# schematic.net
KiCad netlist of a schematic drawn in EAGLE
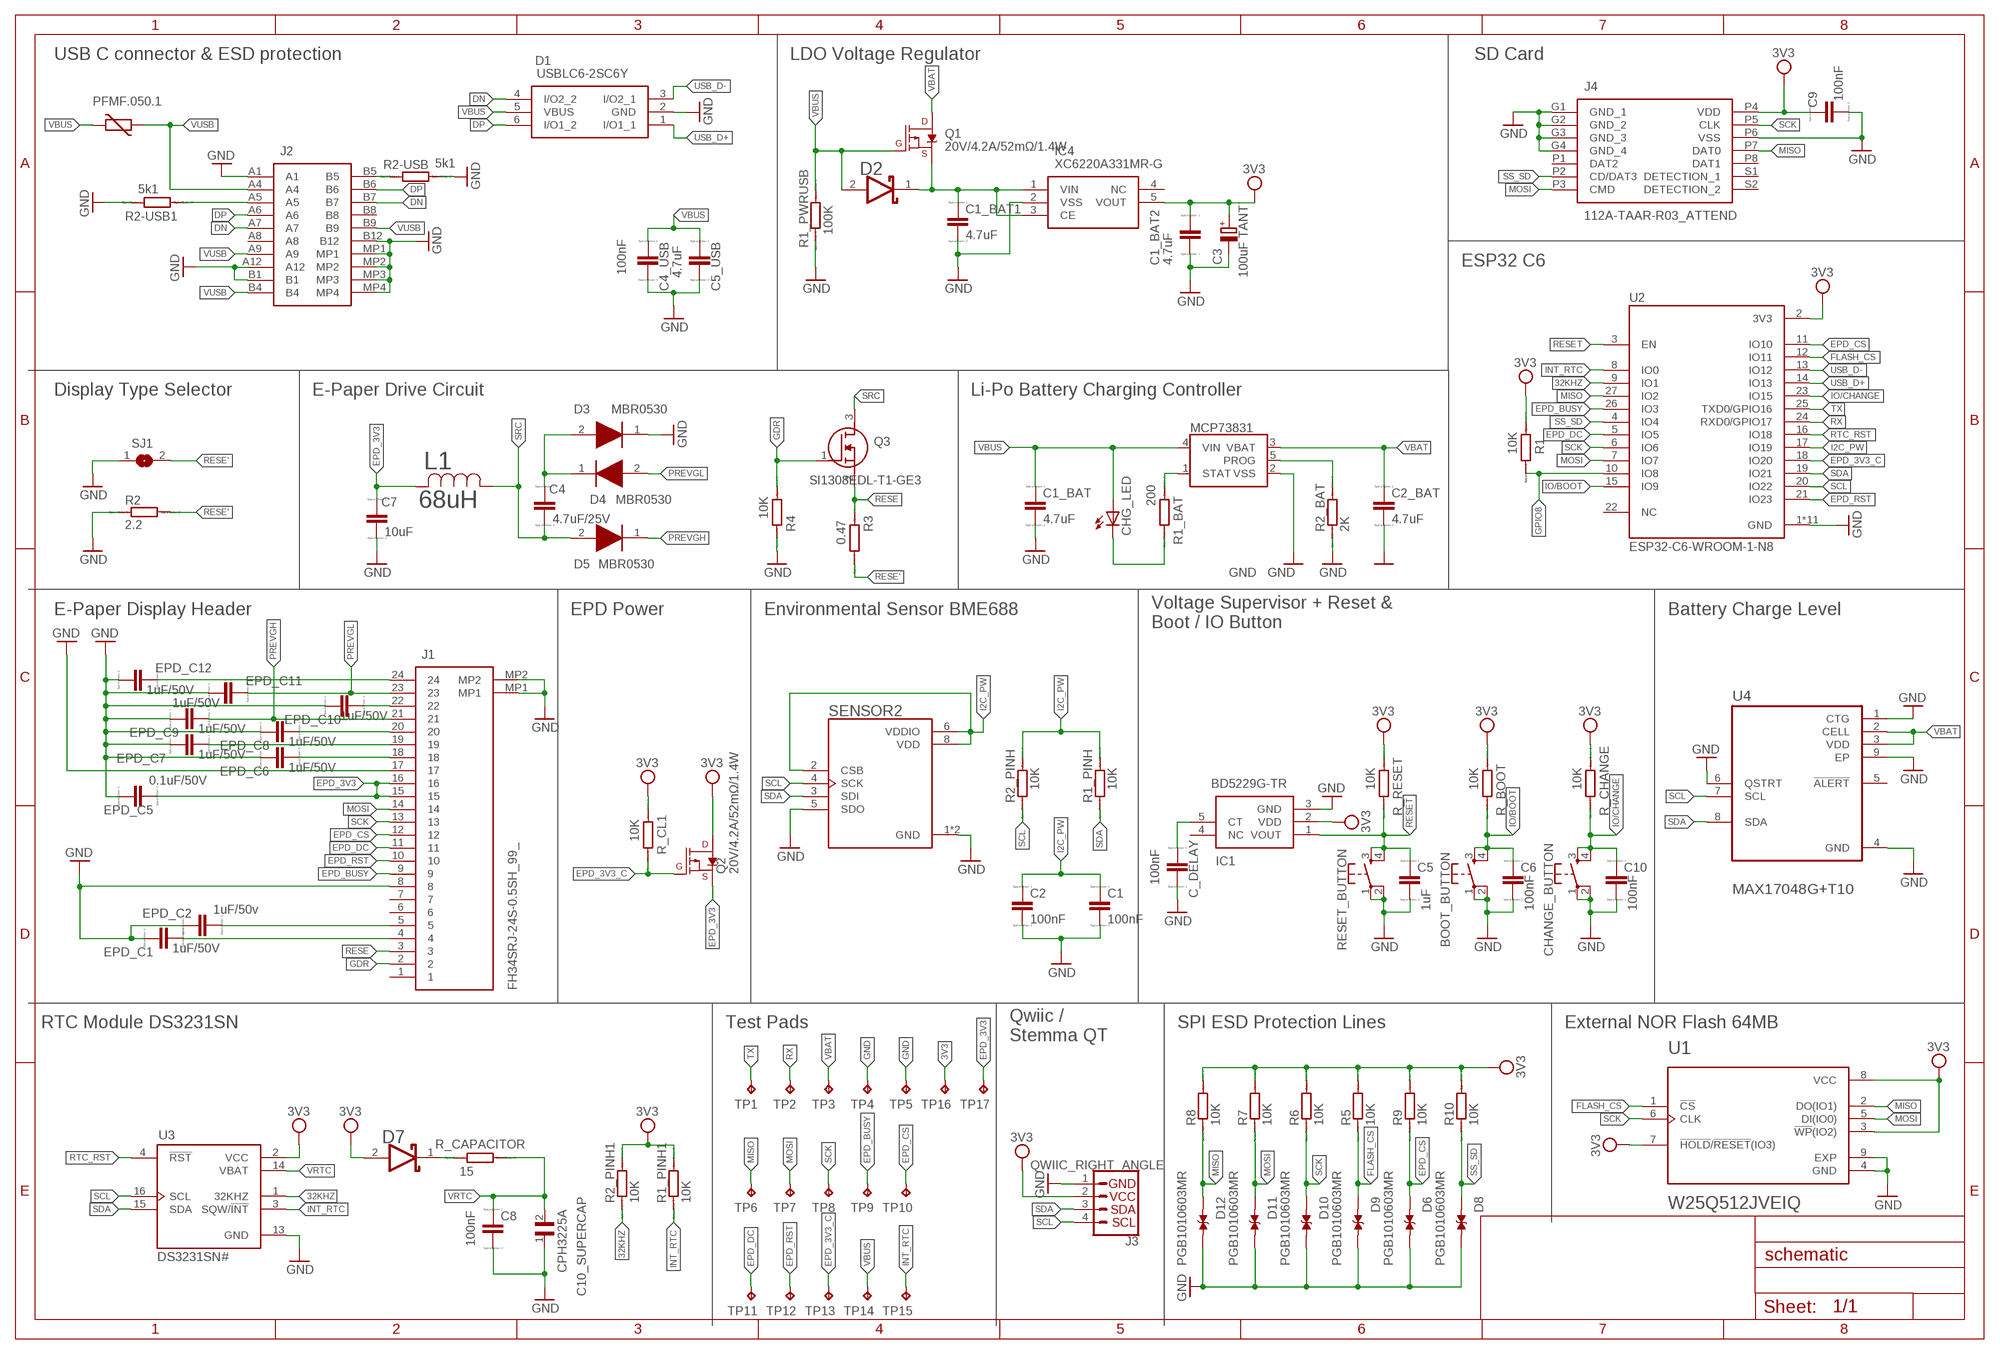
[diagram p0: schematic, sheet 1]

(export (version "E")
  (design (tool "Eeschema 10.0.6"))
  (components
    (comp (ref "BOOT_BUTTON")
      (value "BUTTON_CUSYOMV1")
      (footprint "eagle-import:MYBUTTON")
      (libsource (lib "eagle-import") (part "BUTTON_CUSYOMV1"))
    )
    (comp (ref "C1")
      (value "100nF")
      (footprint "eagle-import:ESP32_WROVER_EAGLE-LTSPICE_C0402")
      (libsource (lib "eagle-import") (part "ESP32_WROVER_EAGLE-LTSPICE_CC0402"))
    )
    (comp (ref "C1_BAT")
      (value "4.7uF")
      (footprint "eagle-import:ESP32_WROVER_EAGLE-LTSPICE_C0402")
      (libsource (lib "eagle-import") (part "ESP32_WROVER_EAGLE-LTSPICE_CC0402"))
    )
    (comp (ref "C1_BAT1")
      (value "4.7uF")
      (footprint "eagle-import:ESP32_WROVER_EAGLE-LTSPICE_C0402")
      (libsource (lib "eagle-import") (part "ESP32_WROVER_EAGLE-LTSPICE_CC0402"))
    )
    (comp (ref "C1_BAT2")
      (value "4.7uF")
      (footprint "eagle-import:ESP32_WROVER_EAGLE-LTSPICE_C0402")
      (libsource (lib "eagle-import") (part "ESP32_WROVER_EAGLE-LTSPICE_CC0402"))
    )
    (comp (ref "C2")
      (value "100nF")
      (footprint "eagle-import:ESP32_WROVER_EAGLE-LTSPICE_C0402")
      (libsource (lib "eagle-import") (part "ESP32_WROVER_EAGLE-LTSPICE_CC0402"))
    )
    (comp (ref "C2_BAT")
      (value "4.7uF")
      (footprint "eagle-import:ESP32_WROVER_EAGLE-LTSPICE_C0402")
      (libsource (lib "eagle-import") (part "ESP32_WROVER_EAGLE-LTSPICE_CC0402"))
    )
    (comp (ref "C3")
      (value "100uF TANT")
      (footprint "eagle-import:RCL_CT3528")
      (libsource (lib "eagle-import") (part "RCL_CPOL-EUCT3528"))
    )
    (comp (ref "C4")
      (value "4.7uF/25V")
      (footprint "eagle-import:EAGLE-LTSPICE_C0402")
      (libsource (lib "eagle-import") (part "EAGLE-LTSPICE_CC0402"))
    )
    (comp (ref "C4_USB")
      (value "100nF")
      (footprint "eagle-import:EAGLE-LTSPICE_C0402")
      (libsource (lib "eagle-import") (part "EAGLE-LTSPICE_CC0402"))
    )
    (comp (ref "C5")
      (value "1uF")
      (footprint "eagle-import:ESP32_WROVER_EAGLE-LTSPICE_C0402")
      (libsource (lib "eagle-import") (part "ESP32_WROVER_EAGLE-LTSPICE_CC0402"))
    )
    (comp (ref "C5_USB")
      (value "4.7uF")
      (footprint "eagle-import:EAGLE-LTSPICE_C0402")
      (libsource (lib "eagle-import") (part "EAGLE-LTSPICE_CC0402"))
    )
    (comp (ref "C6")
      (value "100nF")
      (footprint "eagle-import:ESP32_WROVER_EAGLE-LTSPICE_C0402")
      (libsource (lib "eagle-import") (part "ESP32_WROVER_EAGLE-LTSPICE_CC0402"))
    )
    (comp (ref "C7")
      (value "10uF")
      (footprint "eagle-import:EAGLE-LTSPICE_C0402")
      (libsource (lib "eagle-import") (part "EAGLE-LTSPICE_CC0402"))
    )
    (comp (ref "C8")
      (value "100nF")
      (footprint "eagle-import:ESP32_WROVER_EAGLE-LTSPICE_C0402")
      (libsource (lib "eagle-import") (part "ESP32_WROVER_EAGLE-LTSPICE_CC0402"))
    )
    (comp (ref "C9")
      (value "100nF")
      (footprint "eagle-import:ESP32_WROVER_EAGLE-LTSPICE_C0402")
      (libsource (lib "eagle-import") (part "ESP32_WROVER_EAGLE-LTSPICE_CC0402"))
    )
    (comp (ref "C10")
      (value "100nF")
      (footprint "eagle-import:ESP32_WROVER_EAGLE-LTSPICE_C0402")
      (libsource (lib "eagle-import") (part "ESP32_WROVER_EAGLE-LTSPICE_CC0402"))
    )
    (comp (ref "C10_SUPERCAP")
      (value "CPH3225A")
      (footprint "eagle-import:CAPCP3225X100N")
      (fields (field (name "MF") "Seiko Instruments"))
      (libsource (lib "eagle-import") (part "CPH3225A"))
    )
    (comp (ref "CHANGE_BUTTON")
      (value "BUTTON_CUSYOMV1")
      (footprint "eagle-import:MYBUTTON")
      (libsource (lib "eagle-import") (part "BUTTON_CUSYOMV1"))
    )
    (comp (ref "CHG_LED")
      (value "ADAFRUIT_LEDCHIP-LED0603")
      (footprint "eagle-import:ADAFRUIT_CHIP-LED0603")
      (libsource (lib "eagle-import") (part "ADAFRUIT_LEDCHIP-LED0603"))
    )
    (comp (ref "C_DELAY")
      (value "100nF")
      (footprint "eagle-import:ESP32_WROVER_EAGLE-LTSPICE_C0402")
      (libsource (lib "eagle-import") (part "ESP32_WROVER_EAGLE-LTSPICE_CC0402"))
    )
    (comp (ref "D1")
      (value "USBLC6-2SC6Y")
      (footprint "eagle-import:SOT95P280X145-6N")
      (fields (field (name "MF") "STMicroelectronics"))
      (libsource (lib "eagle-import") (part "USBLC6-2SC6Y"))
    )
    (comp (ref "D2")
      (value "ESP32_WROVER_AVX---SD0805S020S1R0_AVX_SD0805S020S1R0_0_0AVX_SD0805S020S1R0_0_0")
      (footprint "eagle-import:ESP32_WROVER_AVX---SD0805S020S1R0_AVX_SD0805S020S1R0_0")
      (fields
        (field (name "DIGIKEY_PART_NUMBER") "478-7800-1-ND")
        (field (name "MF") "AVX")
        (field (name "MOUSER_PART_NUMBER") "581-SD0805S020S1R0")
      )
      (libsource (lib "eagle-import") (part "ESP32_WROVER_AVX---SD0805S020S1R0_AVX_SD0805S020S1R0_0_0AVX_SD0805S020S1R0_0_0"))
    )
    (comp (ref "D3")
      (value "MBR0530")
      (footprint "eagle-import:SOD3716X135N")
      (fields (field (name "MF") "ON Semiconductor"))
      (libsource (lib "eagle-import") (part "MBR0530"))
    )
    (comp (ref "D4")
      (value "MBR0530")
      (footprint "eagle-import:SOD3716X135N")
      (fields (field (name "MF") "ON Semiconductor"))
      (libsource (lib "eagle-import") (part "MBR0530"))
    )
    (comp (ref "D5")
      (value "MBR0530")
      (footprint "eagle-import:SOD3716X135N")
      (fields (field (name "MF") "ON Semiconductor"))
      (libsource (lib "eagle-import") (part "MBR0530"))
    )
    (comp (ref "D6")
      (value "PGB1010603MR")
      (footprint "eagle-import:DIOC1608X36N")
      (fields (field (name "MF") "Littelfuse Inc."))
      (libsource (lib "eagle-import") (part "PGB1010603MR"))
    )
    (comp (ref "D7")
      (value "ESP32_WROVER_AVX---SD0805S020S1R0_AVX_SD0805S020S1R0_0_0AVX_SD0805S020S1R0_0_0")
      (footprint "eagle-import:ESP32_WROVER_AVX---SD0805S020S1R0_AVX_SD0805S020S1R0_0")
      (fields
        (field (name "DIGIKEY_PART_NUMBER") "478-7800-1-ND")
        (field (name "MF") "AVX")
        (field (name "MOUSER_PART_NUMBER") "581-SD0805S020S1R0")
      )
      (libsource (lib "eagle-import") (part "ESP32_WROVER_AVX---SD0805S020S1R0_AVX_SD0805S020S1R0_0_0AVX_SD0805S020S1R0_0_0"))
    )
    (comp (ref "D8")
      (value "PGB1010603MR")
      (footprint "eagle-import:DIOC1608X36N")
      (fields (field (name "MF") "Littelfuse Inc."))
      (libsource (lib "eagle-import") (part "PGB1010603MR"))
    )
    (comp (ref "D9")
      (value "PGB1010603MR")
      (footprint "eagle-import:DIOC1608X36N")
      (fields (field (name "MF") "Littelfuse Inc."))
      (libsource (lib "eagle-import") (part "PGB1010603MR"))
    )
    (comp (ref "D10")
      (value "PGB1010603MR")
      (footprint "eagle-import:DIOC1608X36N")
      (fields (field (name "MF") "Littelfuse Inc."))
      (libsource (lib "eagle-import") (part "PGB1010603MR"))
    )
    (comp (ref "D11")
      (value "PGB1010603MR")
      (footprint "eagle-import:DIOC1608X36N")
      (fields (field (name "MF") "Littelfuse Inc."))
      (libsource (lib "eagle-import") (part "PGB1010603MR"))
    )
    (comp (ref "D12")
      (value "PGB1010603MR")
      (footprint "eagle-import:DIOC1608X36N")
      (fields (field (name "MF") "Littelfuse Inc."))
      (libsource (lib "eagle-import") (part "PGB1010603MR"))
    )
    (comp (ref "EPD_C1")
      (value "1uF/50V")
      (footprint "eagle-import:EAGLE-LTSPICE_C0402")
      (libsource (lib "eagle-import") (part "EAGLE-LTSPICE_CC0402"))
    )
    (comp (ref "EPD_C2")
      (value "1uF/50v")
      (footprint "eagle-import:EAGLE-LTSPICE_C0402")
      (libsource (lib "eagle-import") (part "EAGLE-LTSPICE_CC0402"))
    )
    (comp (ref "EPD_C5")
      (value "0.1uF/50V")
      (footprint "eagle-import:EAGLE-LTSPICE_C0402")
      (libsource (lib "eagle-import") (part "EAGLE-LTSPICE_CC0402"))
    )
    (comp (ref "EPD_C6")
      (value "1uF/50V")
      (footprint "eagle-import:EAGLE-LTSPICE_C0402")
      (libsource (lib "eagle-import") (part "EAGLE-LTSPICE_CC0402"))
    )
    (comp (ref "EPD_C7")
      (value "1uF/50V")
      (footprint "eagle-import:EAGLE-LTSPICE_C0402")
      (libsource (lib "eagle-import") (part "EAGLE-LTSPICE_CC0402"))
    )
    (comp (ref "EPD_C8")
      (value "1uF/50V")
      (footprint "eagle-import:EAGLE-LTSPICE_C0402")
      (libsource (lib "eagle-import") (part "EAGLE-LTSPICE_CC0402"))
    )
    (comp (ref "EPD_C9")
      (value "1uF/50V")
      (footprint "eagle-import:EAGLE-LTSPICE_C0402")
      (libsource (lib "eagle-import") (part "EAGLE-LTSPICE_CC0402"))
    )
    (comp (ref "EPD_C10")
      (value "1uF/50V")
      (footprint "eagle-import:EAGLE-LTSPICE_C0402")
      (libsource (lib "eagle-import") (part "EAGLE-LTSPICE_CC0402"))
    )
    (comp (ref "EPD_C11")
      (value "1uF/50V")
      (footprint "eagle-import:EAGLE-LTSPICE_C0402")
      (libsource (lib "eagle-import") (part "EAGLE-LTSPICE_CC0402"))
    )
    (comp (ref "EPD_C12")
      (value "1uF/50V")
      (footprint "eagle-import:EAGLE-LTSPICE_C0402")
      (libsource (lib "eagle-import") (part "EAGLE-LTSPICE_CC0402"))
    )
    (comp (ref "IC1")
      (value "BD5229G-TR")
      (footprint "eagle-import:SOT95P280X125-5N")
      (fields (field (name "MOUSER_PART_NUMBER") "755-BD5229G-TR"))
      (libsource (lib "eagle-import") (part "BD5229G-TR"))
    )
    (comp (ref "IC4")
      (value "XC6220A331MR-G")
      (footprint "eagle-import:SOT95P280X120-5N")
      (fields (field (name "MOUSER_PART_NUMBER") "865-XC6220A331MR-G"))
      (libsource (lib "eagle-import") (part "XC6220A331MR-G"))
    )
    (comp (ref "J1")
      (value "FH34SRJ-24S-0.5SH_99_")
      (footprint "eagle-import:FH34SRJ24S05SH99")
      (fields
        (field (name "MANUFACTURER_PART_NUMBER") "FH34SRJ-24S-0.5SH(99)")
        (field (name "MOUSER_PART_NUMBER") "798-FH34SRJ24S05SH99")
      )
      (libsource (lib "eagle-import") (part "FH34SRJ-24S-0.5SH_99_"))
    )
    (comp (ref "J2")
      (value "SAMACSYS_PARTS_USB4110-GF-A")
      (footprint "eagle-import:SAMACSYS_PARTS_USB4110GFA")
      (fields
        (field (name "MANUFACTURER_PART_NUMBER") "USB4110-GF-A")
        (field (name "MOUSER_PART_NUMBER") "640-USB4110-GF-A")
      )
      (libsource (lib "eagle-import") (part "SAMACSYS_PARTS_USB4110-GF-A"))
    )
    (comp (ref "J3")
      (value "QWIIC_RIGHT_ANGLE")
      (footprint "eagle-import:JST04_1MM_RA")
      (libsource (lib "eagle-import") (part "QWIIC_CONNECTORJS-1MM"))
    )
    (comp (ref "J4")
      (value "112A-TAAR-R03_ATTEND")
      (footprint "eagle-import:112ATAARR03ATTEND")
      (fields (field (name "MANUFACTURER_PART_NUMBER") "112A-TAAR-R03 ATTEND"))
      (libsource (lib "eagle-import") (part "112A-TAAR-R03_ATTEND"))
    )
    (comp (ref "L1")
      (value "68uH")
      (footprint "eagle-import:IND_4828-WE-TPC_WRE")
      (fields
        (field (name "MANUFACTURER_PART_NUMBER") "744043680")
        (field (name "COPYRIGHT") "Copyright (C) 2024 Ultra Librarian. All rights reserved.")
      )
      (libsource (lib "eagle-import") (part "744043680IND_4828-WE-TPC_WRE"))
    )
    (comp (ref "MCP73831")
      (value "ESP32_WROVER_SPARKFUN-IC-POWER_MCP73831")
      (footprint "eagle-import:ESP32_WROVER_SPARKFUN-IC-POWER_SOT23-5")
      (libsource (lib "eagle-import") (part "ESP32_WROVER_SPARKFUN-IC-POWER_MCP73831"))
    )
    (comp (ref "PFMF.050.1")
      (value "ESP32C6_VARISTORCN1812")
      (footprint "eagle-import:ESP32C6_VARISTOR_CT_CN1812")
      (libsource (lib "eagle-import") (part "ESP32C6_VARISTORCN1812"))
    )
    (comp (ref "Q1")
      (value "20V/4.2A/52mΩ/1.4W")
      (footprint "eagle-import:ESP32_WROVER_SPARKFUN-DISCRETESEMI_SOT23-3")
      (libsource (lib "eagle-import") (part "ESP32_WROVER_SPARKFUN-DISCRETESEMI_MOSFET_PCH-DMG2305UX-7"))
    )
    (comp (ref "Q2")
      (value "20V/4.2A/52mΩ/1.4W")
      (footprint "eagle-import:ESP32_WROVER_SPARKFUN-DISCRETESEMI_SOT23-3")
      (libsource (lib "eagle-import") (part "ESP32_WROVER_SPARKFUN-DISCRETESEMI_MOSFET_PCH-DMG2305UX-7"))
    )
    (comp (ref "Q3")
      (value "SI1308EDL-T1-GE3")
      (footprint "eagle-import:SOT65P210X110-3N")
      (fields (field (name "MF") "Vishay Siliconix"))
      (libsource (lib "eagle-import") (part "SI1308EDL-T1-GE3"))
    )
    (comp (ref "R1")
      (value "10K")
      (footprint "eagle-import:ESP32_WROVER_EAGLE-LTSPICE_R0402")
      (libsource (lib "eagle-import") (part "ESP32_WROVER_EAGLE-LTSPICE_RR0402"))
    )
    (comp (ref "R1_BAT")
      (value "200")
      (footprint "eagle-import:ESP32_WROVER_EAGLE-LTSPICE_R0402")
      (libsource (lib "eagle-import") (part "ESP32_WROVER_EAGLE-LTSPICE_RR0402"))
    )
    (comp (ref "R1_PINH")
      (value "10K")
      (footprint "eagle-import:ESP32_WROVER_EAGLE-LTSPICE_R0402")
      (libsource (lib "eagle-import") (part "ESP32_WROVER_EAGLE-LTSPICE_RR0402"))
    )
    (comp (ref "R1_PINH1")
      (value "10K")
      (footprint "eagle-import:ESP32_WROVER_EAGLE-LTSPICE_R0402")
      (libsource (lib "eagle-import") (part "ESP32_WROVER_EAGLE-LTSPICE_RR0402"))
    )
    (comp (ref "R1_PWRUSB")
      (value "100K")
      (footprint "eagle-import:ESP32_WROVER_EAGLE-LTSPICE_R0402")
      (libsource (lib "eagle-import") (part "ESP32_WROVER_EAGLE-LTSPICE_RR0402"))
    )
    (comp (ref "R2")
      (value "2.2")
      (footprint "eagle-import:ESP32_WROVER_EAGLE-LTSPICE_R0402")
      (libsource (lib "eagle-import") (part "ESP32_WROVER_EAGLE-LTSPICE_RR0402"))
    )
    (comp (ref "R2-USB")
      (value "5k1")
      (footprint "eagle-import:ESP32_WROVER_EAGLE-LTSPICE_R0402")
      (libsource (lib "eagle-import") (part "ESP32_WROVER_EAGLE-LTSPICE_RR0402"))
    )
    (comp (ref "R2-USB1")
      (value "5k1")
      (footprint "eagle-import:ESP32_WROVER_EAGLE-LTSPICE_R0402")
      (libsource (lib "eagle-import") (part "ESP32_WROVER_EAGLE-LTSPICE_RR0402"))
    )
    (comp (ref "R2_BAT")
      (value "2K")
      (footprint "eagle-import:ESP32_WROVER_EAGLE-LTSPICE_R0402")
      (libsource (lib "eagle-import") (part "ESP32_WROVER_EAGLE-LTSPICE_RR0402"))
    )
    (comp (ref "R2_PINH")
      (value "10K")
      (footprint "eagle-import:ESP32_WROVER_EAGLE-LTSPICE_R0402")
      (libsource (lib "eagle-import") (part "ESP32_WROVER_EAGLE-LTSPICE_RR0402"))
    )
    (comp (ref "R2_PINH1")
      (value "10K")
      (footprint "eagle-import:ESP32_WROVER_EAGLE-LTSPICE_R0402")
      (libsource (lib "eagle-import") (part "ESP32_WROVER_EAGLE-LTSPICE_RR0402"))
    )
    (comp (ref "R3")
      (value "0.47")
      (footprint "eagle-import:ESP32_WROVER_EAGLE-LTSPICE_R0402")
      (libsource (lib "eagle-import") (part "ESP32_WROVER_EAGLE-LTSPICE_RR0402"))
    )
    (comp (ref "R4")
      (value "10K")
      (footprint "eagle-import:ESP32_WROVER_EAGLE-LTSPICE_R0402")
      (libsource (lib "eagle-import") (part "ESP32_WROVER_EAGLE-LTSPICE_RR0402"))
    )
    (comp (ref "R5")
      (value "10K")
      (footprint "eagle-import:ESP32_WROVER_EAGLE-LTSPICE_R0402")
      (libsource (lib "eagle-import") (part "ESP32_WROVER_EAGLE-LTSPICE_RR0402"))
    )
    (comp (ref "R6")
      (value "10K")
      (footprint "eagle-import:ESP32_WROVER_EAGLE-LTSPICE_R0402")
      (libsource (lib "eagle-import") (part "ESP32_WROVER_EAGLE-LTSPICE_RR0402"))
    )
    (comp (ref "R7")
      (value "10K")
      (footprint "eagle-import:ESP32_WROVER_EAGLE-LTSPICE_R0402")
      (libsource (lib "eagle-import") (part "ESP32_WROVER_EAGLE-LTSPICE_RR0402"))
    )
    (comp (ref "R8")
      (value "10K")
      (footprint "eagle-import:ESP32_WROVER_EAGLE-LTSPICE_R0402")
      (libsource (lib "eagle-import") (part "ESP32_WROVER_EAGLE-LTSPICE_RR0402"))
    )
    (comp (ref "R9")
      (value "10K")
      (footprint "eagle-import:ESP32_WROVER_EAGLE-LTSPICE_R0402")
      (libsource (lib "eagle-import") (part "ESP32_WROVER_EAGLE-LTSPICE_RR0402"))
    )
    (comp (ref "R10")
      (value "10K")
      (footprint "eagle-import:ESP32_WROVER_EAGLE-LTSPICE_R0402")
      (libsource (lib "eagle-import") (part "ESP32_WROVER_EAGLE-LTSPICE_RR0402"))
    )
    (comp (ref "RESET_BUTTON")
      (value "BUTTON_CUSYOMV1")
      (footprint "eagle-import:MYBUTTON")
      (libsource (lib "eagle-import") (part "BUTTON_CUSYOMV1"))
    )
    (comp (ref "R_BOOT")
      (value "10K")
      (footprint "eagle-import:ESP32_WROVER_EAGLE-LTSPICE_R0402")
      (libsource (lib "eagle-import") (part "ESP32_WROVER_EAGLE-LTSPICE_RR0402"))
    )
    (comp (ref "R_CAPACITOR")
      (value "15")
      (footprint "eagle-import:ESP32_WROVER_EAGLE-LTSPICE_R0402")
      (libsource (lib "eagle-import") (part "ESP32_WROVER_EAGLE-LTSPICE_RR0402"))
    )
    (comp (ref "R_CHANGE")
      (value "10K")
      (footprint "eagle-import:ESP32_WROVER_EAGLE-LTSPICE_R0402")
      (libsource (lib "eagle-import") (part "ESP32_WROVER_EAGLE-LTSPICE_RR0402"))
    )
    (comp (ref "R_CL1")
      (value "10K")
      (footprint "eagle-import:ESP32_WROVER_EAGLE-LTSPICE_R0402")
      (libsource (lib "eagle-import") (part "ESP32_WROVER_EAGLE-LTSPICE_RR0402"))
    )
    (comp (ref "R_RESET")
      (value "10K")
      (footprint "eagle-import:ESP32_WROVER_EAGLE-LTSPICE_R0402")
      (libsource (lib "eagle-import") (part "ESP32_WROVER_EAGLE-LTSPICE_RR0402"))
    )
    (comp (ref "SENSOR2")
      (value "ESP32_WROVER_BME680_BME680")
      (footprint "eagle-import:ESP32_WROVER_BME680_PSON80P300X300X100-8N")
      (fields (field (name "MF") "Bosch Sensortec") (field (name "MP") "BME680"))
      (libsource (lib "eagle-import") (part "ESP32_WROVER_BME680_BME680"))
    )
    (comp (ref "SJ1") (value "SJ") (footprint "eagle-import:SJ") (libsource (lib "eagle-import") (part "SJ")))
    (comp (ref "TP1")
      (value "TPTP20R")
      (footprint "eagle-import:TP20R")
      (libsource (lib "eagle-import") (part "TPTP20R"))
    )
    (comp (ref "TP2")
      (value "TPTP20R")
      (footprint "eagle-import:TP20R")
      (libsource (lib "eagle-import") (part "TPTP20R"))
    )
    (comp (ref "TP3")
      (value "TPTP20R")
      (footprint "eagle-import:TP20R")
      (libsource (lib "eagle-import") (part "TPTP20R"))
    )
    (comp (ref "TP4")
      (value "TPTP20R")
      (footprint "eagle-import:TP20R")
      (libsource (lib "eagle-import") (part "TPTP20R"))
    )
    (comp (ref "TP5")
      (value "TPTP20R")
      (footprint "eagle-import:TP20R")
      (libsource (lib "eagle-import") (part "TPTP20R"))
    )
    (comp (ref "TP6")
      (value "TPTP20R")
      (footprint "eagle-import:TP20R")
      (libsource (lib "eagle-import") (part "TPTP20R"))
    )
    (comp (ref "TP7")
      (value "TPTP20R")
      (footprint "eagle-import:TP20R")
      (libsource (lib "eagle-import") (part "TPTP20R"))
    )
    (comp (ref "TP8")
      (value "TPTP20R")
      (footprint "eagle-import:TP20R")
      (libsource (lib "eagle-import") (part "TPTP20R"))
    )
    (comp (ref "TP9")
      (value "TPTP20R")
      (footprint "eagle-import:TP20R")
      (libsource (lib "eagle-import") (part "TPTP20R"))
    )
    (comp (ref "TP10")
      (value "TPTP20R")
      (footprint "eagle-import:TP20R")
      (libsource (lib "eagle-import") (part "TPTP20R"))
    )
    (comp (ref "TP11")
      (value "TPTP20R")
      (footprint "eagle-import:TP20R")
      (libsource (lib "eagle-import") (part "TPTP20R"))
    )
    (comp (ref "TP12")
      (value "TPTP20R")
      (footprint "eagle-import:TP20R")
      (libsource (lib "eagle-import") (part "TPTP20R"))
    )
    (comp (ref "TP13")
      (value "TPTP20R")
      (footprint "eagle-import:TP20R")
      (libsource (lib "eagle-import") (part "TPTP20R"))
    )
    (comp (ref "TP14")
      (value "TPTP20R")
      (footprint "eagle-import:TP20R")
      (libsource (lib "eagle-import") (part "TPTP20R"))
    )
    (comp (ref "TP15")
      (value "TPTP20R")
      (footprint "eagle-import:TP20R")
      (libsource (lib "eagle-import") (part "TPTP20R"))
    )
    (comp (ref "TP16")
      (value "TPTP20R")
      (footprint "eagle-import:TP20R")
      (libsource (lib "eagle-import") (part "TPTP20R"))
    )
    (comp (ref "TP17")
      (value "TPTP20R")
      (footprint "eagle-import:TP20R")
      (libsource (lib "eagle-import") (part "TPTP20R"))
    )
    (comp (ref "U1")
      (value "W25Q512JVEIQ")
      (footprint "eagle-import:SON127P600X800X80-9N")
      (fields (field (name "MF") "Winbond Electronics"))
      (libsource (lib "eagle-import") (part "W25Q512JVEIQ"))
    )
    (comp (ref "U2")
      (value "ESP32-C6-WROOM-1-N8")
      (footprint "eagle-import:XCVR_ESP32-C6-WROOM-1-N8")
      (fields (field (name "MF") "Espressif Systems"))
      (libsource (lib "eagle-import") (part "ESP32-C6-WROOM-1-N8"))
    )
    (comp (ref "U3")
      (value "DS3231SN#")
      (footprint "eagle-import:SOIC127P1032X265-16N")
      (fields (field (name "MF") "Analog Devices"))
      (libsource (lib "eagle-import") (part "DS3231SN#"))
    )
    (comp (ref "U4")
      (value "MAX17048G+T10")
      (footprint "eagle-import:SON50P200X200X80-9N")
      (fields (field (name "MF") "Analog Devices"))
      (libsource (lib "eagle-import") (part "MAX17048G+T10"))
    )
  )
  (nets
    (net (code "1") (name "3V3") (class "Default")
      (node (ref "C1_BAT2") (pin "1") (pinfunction "1_1") (pintype "passive"))
      (node (ref "C3") (pin "+") (pinfunction "+_+") (pintype "passive"))
      (node (ref "C9") (pin "1") (pinfunction "1_1") (pintype "passive"))
      (node (ref "D7") (pin "2") (pinfunction "ANODE_2") (pintype "bidirectional"))
      (node (ref "IC1") (pin "2") (pinfunction "VDD_2") (pintype "bidirectional"))
      (node (ref "IC4") (pin "5") (pinfunction "VOUT_5") (pintype "bidirectional"))
      (node (ref "J3") (pin "2") (pinfunction "2_2") (pintype "power_in"))
      (node (ref "J4") (pin "P4") (pinfunction "VDD_P4") (pintype "bidirectional"))
      (node (ref "Q2") (pin "3") (pinfunction "D_3") (pintype "bidirectional"))
      (node (ref "R1") (pin "2") (pinfunction "2_2") (pintype "passive"))
      (node (ref "R10") (pin "2") (pinfunction "2_2") (pintype "passive"))
      (node (ref "R1_PINH1") (pin "2") (pinfunction "2_2") (pintype "passive"))
      (node (ref "R2_PINH1") (pin "2") (pinfunction "2_2") (pintype "passive"))
      (node (ref "R5") (pin "2") (pinfunction "2_2") (pintype "passive"))
      (node (ref "R6") (pin "2") (pinfunction "2_2") (pintype "passive"))
      (node (ref "R7") (pin "2") (pinfunction "2_2") (pintype "passive"))
      (node (ref "R8") (pin "2") (pinfunction "2_2") (pintype "passive"))
      (node (ref "R9") (pin "2") (pinfunction "2_2") (pintype "passive"))
      (node (ref "R_BOOT") (pin "2") (pinfunction "2_2") (pintype "passive"))
      (node (ref "R_CHANGE") (pin "2") (pinfunction "2_2") (pintype "passive"))
      (node (ref "R_CL1") (pin "2") (pinfunction "2_2") (pintype "passive"))
      (node (ref "R_RESET") (pin "2") (pinfunction "2_2") (pintype "passive"))
      (node (ref "TP16") (pin "TP") (pinfunction "TP_TP") (pintype "input"))
      (node (ref "U1") (pin "3") (pinfunction "~{WP}(IO2)_3") (pintype "bidirectional"))
      (node (ref "U1") (pin "7") (pinfunction "~{HOLD}/~{RESET}(IO3)_7") (pintype "bidirectional"))
      (node (ref "U1") (pin "8") (pinfunction "VCC_8") (pintype "power_in"))
      (node (ref "U2") (pin "2") (pinfunction "3V3_2") (pintype "power_in"))
      (node (ref "U3") (pin "2") (pinfunction "VCC_2") (pintype "power_in"))
    )
    (net (code "2") (name "32KHZ") (class "Default")
      (node (ref "R2_PINH1") (pin "1") (pinfunction "1_1") (pintype "passive"))
      (node (ref "U2") (pin "9") (pinfunction "IO1_9") (pintype "bidirectional"))
      (node (ref "U3") (pin "1") (pinfunction "32KHZ_1") (pintype "output"))
    )
    (net (code "3") (name "DN") (class "Default")
      (node (ref "D1") (pin "4") (pinfunction "I/O2_2_4") (pintype "bidirectional"))
      (node (ref "J2") (pin "A7") (pinfunction "A7_A7") (pintype "bidirectional"))
      (node (ref "J2") (pin "B7") (pinfunction "B7_B7") (pintype "bidirectional"))
    )
    (net (code "4") (name "DP") (class "Default")
      (node (ref "D1") (pin "6") (pinfunction "I/O1_2_6") (pintype "bidirectional"))
      (node (ref "J2") (pin "A6") (pinfunction "A6_A6") (pintype "bidirectional"))
      (node (ref "J2") (pin "B6") (pinfunction "B6_B6") (pintype "bidirectional"))
    )
    (net (code "5") (name "EPD_3V3") (class "Default")
      (node (ref "C7") (pin "1") (pinfunction "1_1") (pintype "passive"))
      (node (ref "EPD_C5") (pin "2") (pinfunction "2_2") (pintype "passive"))
      (node (ref "J1") (pin "15") (pinfunction "15_15") (pintype "bidirectional"))
      (node (ref "J1") (pin "16") (pinfunction "16_16") (pintype "bidirectional"))
      (node (ref "L1") (pin "2") (pinfunction "2_2") (pintype "passive"))
      (node (ref "Q2") (pin "2") (pinfunction "S_2") (pintype "bidirectional"))
      (node (ref "TP17") (pin "TP") (pinfunction "TP_TP") (pintype "input"))
    )
    (net (code "6") (name "EPD_3V3_C") (class "Default")
      (node (ref "Q2") (pin "1") (pinfunction "G_1") (pintype "bidirectional"))
      (node (ref "R_CL1") (pin "1") (pinfunction "1_1") (pintype "passive"))
      (node (ref "TP13") (pin "TP") (pinfunction "TP_TP") (pintype "input"))
      (node (ref "U2") (pin "18") (pinfunction "IO20_18") (pintype "bidirectional"))
    )
    (net (code "7") (name "EPD_BUSY") (class "Default")
      (node (ref "J1") (pin "9") (pinfunction "9_9") (pintype "bidirectional"))
      (node (ref "TP9") (pin "TP") (pinfunction "TP_TP") (pintype "input"))
      (node (ref "U2") (pin "26") (pinfunction "IO3_26") (pintype "bidirectional"))
    )
    (net (code "8") (name "EPD_CS") (class "Default")
      (node (ref "D6") (pin "1") (pinfunction "1_1") (pintype "passive"))
      (node (ref "J1") (pin "12") (pinfunction "12_12") (pintype "bidirectional"))
      (node (ref "R9") (pin "1") (pinfunction "1_1") (pintype "passive"))
      (node (ref "TP10") (pin "TP") (pinfunction "TP_TP") (pintype "input"))
      (node (ref "U2") (pin "11") (pinfunction "IO10_11") (pintype "bidirectional"))
    )
    (net (code "9") (name "EPD_DC") (class "Default")
      (node (ref "J1") (pin "11") (pinfunction "11_11") (pintype "bidirectional"))
      (node (ref "TP11") (pin "TP") (pinfunction "TP_TP") (pintype "input"))
      (node (ref "U2") (pin "5") (pinfunction "IO5_5") (pintype "bidirectional"))
    )
    (net (code "10") (name "EPD_RST") (class "Default")
      (node (ref "J1") (pin "10") (pinfunction "10_10") (pintype "bidirectional"))
      (node (ref "TP12") (pin "TP") (pinfunction "TP_TP") (pintype "input"))
      (node (ref "U2") (pin "21") (pinfunction "IO23_21") (pintype "bidirectional"))
    )
    (net (code "11") (name "FLASH_CS") (class "Default")
      (node (ref "D9") (pin "1") (pinfunction "1_1") (pintype "passive"))
      (node (ref "R5") (pin "1") (pinfunction "1_1") (pintype "passive"))
      (node (ref "U1") (pin "1") (pinfunction "~{CS}_1") (pintype "input"))
      (node (ref "U2") (pin "12") (pinfunction "IO11_12") (pintype "bidirectional"))
    )
    (net (code "12") (name "GDR") (class "Default")
      (node (ref "J1") (pin "2") (pinfunction "2_2") (pintype "bidirectional"))
      (node (ref "Q3") (pin "1") (pinfunction "G_1") (pintype "bidirectional"))
      (node (ref "R4") (pin "2") (pinfunction "2_2") (pintype "passive"))
    )
    (net (code "13") (name "GND") (class "Default")
      (node (ref "BOOT_BUTTON") (pin "1") (pinfunction "1_1") (pintype "passive"))
      (node (ref "BOOT_BUTTON") (pin "2") (pinfunction "2_2") (pintype "passive"))
      (node (ref "C1") (pin "2") (pinfunction "2_2") (pintype "passive"))
      (node (ref "C10") (pin "2") (pinfunction "2_2") (pintype "passive"))
      (node (ref "C10_SUPERCAP") (pin "1") (pinfunction "1_1") (pintype "passive"))
      (node (ref "C1_BAT") (pin "2") (pinfunction "2_2") (pintype "passive"))
      (node (ref "C1_BAT1") (pin "2") (pinfunction "2_2") (pintype "passive"))
      (node (ref "C1_BAT2") (pin "2") (pinfunction "2_2") (pintype "passive"))
      (node (ref "C2") (pin "2") (pinfunction "2_2") (pintype "passive"))
      (node (ref "C2_BAT") (pin "2") (pinfunction "2_2") (pintype "passive"))
      (node (ref "C3") (pin "-") (pinfunction "-_-") (pintype "passive"))
      (node (ref "C4_USB") (pin "2") (pinfunction "2_2") (pintype "passive"))
      (node (ref "C5") (pin "2") (pinfunction "2_2") (pintype "passive"))
      (node (ref "C5_USB") (pin "2") (pinfunction "2_2") (pintype "passive"))
      (node (ref "C6") (pin "2") (pinfunction "2_2") (pintype "passive"))
      (node (ref "C7") (pin "2") (pinfunction "2_2") (pintype "passive"))
      (node (ref "C8") (pin "2") (pinfunction "2_2") (pintype "passive"))
      (node (ref "C9") (pin "2") (pinfunction "2_2") (pintype "passive"))
      (node (ref "CHANGE_BUTTON") (pin "1") (pinfunction "1_1") (pintype "passive"))
      (node (ref "CHANGE_BUTTON") (pin "2") (pinfunction "2_2") (pintype "passive"))
      (node (ref "C_DELAY") (pin "2") (pinfunction "2_2") (pintype "passive"))
      (node (ref "D1") (pin "2") (pinfunction "GND_2") (pintype "bidirectional"))
      (node (ref "D10") (pin "2") (pinfunction "2_2") (pintype "passive"))
      (node (ref "D11") (pin "2") (pinfunction "2_2") (pintype "passive"))
      (node (ref "D12") (pin "2") (pinfunction "2_2") (pintype "passive"))
      (node (ref "D3") (pin "1") (pinfunction "K_1") (pintype "bidirectional"))
      (node (ref "D6") (pin "2") (pinfunction "2_2") (pintype "passive"))
      (node (ref "D8") (pin "2") (pinfunction "2_2") (pintype "passive"))
      (node (ref "D9") (pin "2") (pinfunction "2_2") (pintype "passive"))
      (node (ref "EPD_C1") (pin "1") (pinfunction "1_1") (pintype "passive"))
      (node (ref "EPD_C10") (pin "1") (pinfunction "1_1") (pintype "passive"))
      (node (ref "EPD_C11") (pin "1") (pinfunction "1_1") (pintype "passive"))
      (node (ref "EPD_C12") (pin "1") (pinfunction "1_1") (pintype "passive"))
      (node (ref "EPD_C2") (pin "1") (pinfunction "1_1") (pintype "passive"))
      (node (ref "EPD_C5") (pin "1") (pinfunction "1_1") (pintype "passive"))
      (node (ref "EPD_C6") (pin "1") (pinfunction "1_1") (pintype "passive"))
      (node (ref "EPD_C7") (pin "1") (pinfunction "1_1") (pintype "passive"))
      (node (ref "EPD_C8") (pin "1") (pinfunction "1_1") (pintype "passive"))
      (node (ref "EPD_C9") (pin "1") (pinfunction "1_1") (pintype "passive"))
      (node (ref "IC1") (pin "3") (pinfunction "GND_3") (pintype "bidirectional"))
      (node (ref "IC4") (pin "2") (pinfunction "VSS_2") (pintype "bidirectional"))
      (node (ref "J1") (pin "17") (pinfunction "17_17") (pintype "bidirectional"))
      (node (ref "J1") (pin "8") (pinfunction "8_8") (pintype "bidirectional"))
      (node (ref "J1") (pin "MP1") (pinfunction "MP1_MP1") (pintype "bidirectional"))
      (node (ref "J1") (pin "MP2") (pinfunction "MP2_MP2") (pintype "bidirectional"))
      (node (ref "J2") (pin "A1") (pinfunction "A1_A1") (pintype "bidirectional"))
      (node (ref "J2") (pin "A12") (pinfunction "A12_A12") (pintype "bidirectional"))
      (node (ref "J2") (pin "B1") (pinfunction "B1_B1") (pintype "bidirectional"))
      (node (ref "J2") (pin "B12") (pinfunction "B12_B12") (pintype "bidirectional"))
      (node (ref "J2") (pin "MP1") (pinfunction "MP1_MP1") (pintype "bidirectional"))
      (node (ref "J2") (pin "MP2") (pinfunction "MP2_MP2") (pintype "bidirectional"))
      (node (ref "J2") (pin "MP3") (pinfunction "MP3_MP3") (pintype "bidirectional"))
      (node (ref "J2") (pin "MP4") (pinfunction "MP4_MP4") (pintype "bidirectional"))
      (node (ref "J3") (pin "1") (pinfunction "1_1") (pintype "power_in"))
      (node (ref "J4") (pin "G1") (pinfunction "GND_1_G1") (pintype "bidirectional"))
      (node (ref "J4") (pin "G2") (pinfunction "GND_2_G2") (pintype "bidirectional"))
      (node (ref "J4") (pin "G3") (pinfunction "GND_3_G3") (pintype "bidirectional"))
      (node (ref "J4") (pin "G4") (pinfunction "GND_4_G4") (pintype "bidirectional"))
      (node (ref "J4") (pin "P6") (pinfunction "VSS_P6") (pintype "bidirectional"))
      (node (ref "MCP73831") (pin "2") (pinfunction "VSS_2") (pintype "power_in"))
      (node (ref "R1_PWRUSB") (pin "1") (pinfunction "1_1") (pintype "passive"))
      (node (ref "R2") (pin "1") (pinfunction "1_1") (pintype "passive"))
      (node (ref "R2-USB") (pin "2") (pinfunction "2_2") (pintype "passive"))
      (node (ref "R2-USB1") (pin "1") (pinfunction "1_1") (pintype "passive"))
      (node (ref "R2_BAT") (pin "1") (pinfunction "1_1") (pintype "passive"))
      (node (ref "R4") (pin "1") (pinfunction "1_1") (pintype "passive"))
      (node (ref "RESET_BUTTON") (pin "1") (pinfunction "1_1") (pintype "passive"))
      (node (ref "RESET_BUTTON") (pin "2") (pinfunction "2_2") (pintype "passive"))
      (node (ref "SENSOR2") (pin "1") (pinfunction "GND_1") (pintype "power_in"))
      (node (ref "SENSOR2") (pin "5") (pinfunction "SDO_5") (pintype "bidirectional"))
      (node (ref "SENSOR2") (pin "7") (pinfunction "GND_7") (pintype "power_in"))
      (node (ref "SJ1") (pin "1") (pinfunction "1_1") (pintype "passive"))
      (node (ref "TP4") (pin "TP") (pinfunction "TP_TP") (pintype "input"))
      (node (ref "TP5") (pin "TP") (pinfunction "TP_TP") (pintype "input"))
      (node (ref "U1") (pin "4") (pinfunction "GND_4") (pintype "power_in"))
      (node (ref "U1") (pin "9") (pinfunction "EXP_9") (pintype "passive"))
      (node (ref "U2") (pin "1") (pinfunction "GND_1") (pintype "power_in"))
      (node (ref "U2") (pin "28") (pinfunction "GND_28") (pintype "power_in"))
      (node (ref "U2") (pin "29_1") (pinfunction "GND_29_1") (pintype "power_in"))
      (node (ref "U2") (pin "29_2") (pinfunction "GND_29_2") (pintype "power_in"))
      (node (ref "U2") (pin "29_3") (pinfunction "GND_29_3") (pintype "power_in"))
      (node (ref "U2") (pin "29_4") (pinfunction "GND_29_4") (pintype "power_in"))
      (node (ref "U2") (pin "29_5") (pinfunction "GND_29_5") (pintype "power_in"))
      (node (ref "U2") (pin "29_6") (pinfunction "GND_29_6") (pintype "power_in"))
      (node (ref "U2") (pin "29_7") (pinfunction "GND_29_7") (pintype "power_in"))
      (node (ref "U2") (pin "29_8") (pinfunction "GND_29_8") (pintype "power_in"))
      (node (ref "U2") (pin "29_9") (pinfunction "GND_29_9") (pintype "power_in"))
      (node (ref "U3") (pin "13") (pinfunction "GND_13") (pintype "power_in"))
      (node (ref "U4") (pin "1") (pinfunction "CTG_1") (pintype "power_in"))
      (node (ref "U4") (pin "4") (pinfunction "GND_4") (pintype "power_in"))
      (node (ref "U4") (pin "6") (pinfunction "QSTRT_6") (pintype "input"))
      (node (ref "U4") (pin "9") (pinfunction "EP_9") (pintype "power_in"))
    )
    (net (code "14") (name "GPIO8") (class "Default")
      (node (ref "R1") (pin "1") (pinfunction "1_1") (pintype "passive"))
      (node (ref "U2") (pin "10") (pinfunction "IO8_10") (pintype "bidirectional"))
    )
    (net (code "15") (name "I2C_PW") (class "Default")
      (node (ref "C1") (pin "1") (pinfunction "1_1") (pintype "passive"))
      (node (ref "C2") (pin "1") (pinfunction "1_1") (pintype "passive"))
      (node (ref "R1_PINH") (pin "2") (pinfunction "2_2") (pintype "passive"))
      (node (ref "R2_PINH") (pin "2") (pinfunction "2_2") (pintype "passive"))
      (node (ref "SENSOR2") (pin "2") (pinfunction "CSB_2") (pintype "input"))
      (node (ref "SENSOR2") (pin "6") (pinfunction "VDDIO_6") (pintype "power_in"))
      (node (ref "SENSOR2") (pin "8") (pinfunction "VDD_8") (pintype "power_in"))
      (node (ref "U2") (pin "17") (pinfunction "IO19_17") (pintype "bidirectional"))
    )
    (net (code "16") (name "INT_RTC") (class "Default")
      (node (ref "R1_PINH1") (pin "1") (pinfunction "1_1") (pintype "passive"))
      (node (ref "TP15") (pin "TP") (pinfunction "TP_TP") (pintype "input"))
      (node (ref "U2") (pin "8") (pinfunction "IO0_8") (pintype "bidirectional"))
      (node (ref "U3") (pin "3") (pinfunction "SQW/~{INT}_3") (pintype "output"))
    )
    (net (code "17") (name "IO{slash}BOOT") (class "Default")
      (node (ref "BOOT_BUTTON") (pin "3") (pinfunction "3_3") (pintype "passive"))
      (node (ref "BOOT_BUTTON") (pin "4") (pinfunction "4_4") (pintype "passive"))
      (node (ref "C6") (pin "1") (pinfunction "1_1") (pintype "passive"))
      (node (ref "R_BOOT") (pin "1") (pinfunction "1_1") (pintype "passive"))
      (node (ref "U2") (pin "15") (pinfunction "IO9_15") (pintype "bidirectional"))
    )
    (net (code "18") (name "IO{slash}CHANGE") (class "Default")
      (node (ref "C10") (pin "1") (pinfunction "1_1") (pintype "passive"))
      (node (ref "CHANGE_BUTTON") (pin "3") (pinfunction "3_3") (pintype "passive"))
      (node (ref "CHANGE_BUTTON") (pin "4") (pinfunction "4_4") (pintype "passive"))
      (node (ref "R_CHANGE") (pin "1") (pinfunction "1_1") (pintype "passive"))
      (node (ref "U2") (pin "23") (pinfunction "IO15_23") (pintype "bidirectional"))
    )
    (net (code "19") (name "MISO") (class "Default")
      (node (ref "D12") (pin "1") (pinfunction "1_1") (pintype "passive"))
      (node (ref "J4") (pin "P7") (pinfunction "DAT0_P7") (pintype "bidirectional"))
      (node (ref "R8") (pin "1") (pinfunction "1_1") (pintype "passive"))
      (node (ref "TP6") (pin "TP") (pinfunction "TP_TP") (pintype "input"))
      (node (ref "U1") (pin "2") (pinfunction "DO(IO1)_2") (pintype "bidirectional"))
      (node (ref "U2") (pin "27") (pinfunction "IO2_27") (pintype "bidirectional"))
    )
    (net (code "20") (name "MOSI") (class "Default")
      (node (ref "D11") (pin "1") (pinfunction "1_1") (pintype "passive"))
      (node (ref "J1") (pin "14") (pinfunction "14_14") (pintype "bidirectional"))
      (node (ref "J4") (pin "P3") (pinfunction "CMD_P3") (pintype "bidirectional"))
      (node (ref "R7") (pin "1") (pinfunction "1_1") (pintype "passive"))
      (node (ref "TP7") (pin "TP") (pinfunction "TP_TP") (pintype "input"))
      (node (ref "U1") (pin "5") (pinfunction "DI(IO0)_5") (pintype "bidirectional"))
      (node (ref "U2") (pin "7") (pinfunction "IO7_7") (pintype "bidirectional"))
    )
    (net (code "21") (name "Net-(CHG_LED-PadC)") (class "Default")
      (node (ref "CHG_LED") (pin "C") (pinfunction "C_C") (pintype "passive"))
      (node (ref "R1_BAT") (pin "1") (pinfunction "1_1") (pintype "passive"))
    )
    (net (code "22") (name "Net-(D2-CATHODE)") (class "Default")
      (node (ref "C1_BAT1") (pin "1") (pinfunction "1_1") (pintype "passive"))
      (node (ref "D2") (pin "1") (pinfunction "CATHODE_1") (pintype "bidirectional"))
      (node (ref "IC4") (pin "1") (pinfunction "VIN_1") (pintype "bidirectional"))
      (node (ref "IC4") (pin "3") (pinfunction "CE_3") (pintype "bidirectional"))
      (node (ref "Q1") (pin "2") (pinfunction "S_2") (pintype "bidirectional"))
    )
    (net (code "23") (name "Net-(D3-A)") (class "Default")
      (node (ref "C4") (pin "1") (pinfunction "1_1") (pintype "passive"))
      (node (ref "D3") (pin "2") (pinfunction "A_2") (pintype "bidirectional"))
      (node (ref "D4") (pin "1") (pinfunction "K_1") (pintype "bidirectional"))
    )
    (net (code "24") (name "Net-(D7-CATHODE)") (class "Default")
      (node (ref "D7") (pin "1") (pinfunction "CATHODE_1") (pintype "bidirectional"))
      (node (ref "R_CAPACITOR") (pin "2") (pinfunction "2_2") (pintype "passive"))
    )
    (net (code "25") (name "Net-(EPD_C1-Pad2)") (class "Default")
      (node (ref "EPD_C1") (pin "2") (pinfunction "2_2") (pintype "passive"))
      (node (ref "J1") (pin "4") (pinfunction "4_4") (pintype "bidirectional"))
    )
    (net (code "26") (name "Net-(EPD_C2-Pad2)") (class "Default")
      (node (ref "EPD_C2") (pin "2") (pinfunction "2_2") (pintype "passive"))
      (node (ref "J1") (pin "5") (pinfunction "5_5") (pintype "bidirectional"))
    )
    (net (code "27") (name "Net-(EPD_C6-Pad2)") (class "Default")
      (node (ref "EPD_C6") (pin "2") (pinfunction "2_2") (pintype "passive"))
      (node (ref "J1") (pin "18") (pinfunction "18_18") (pintype "bidirectional"))
    )
    (net (code "28") (name "Net-(EPD_C7-Pad2)") (class "Default")
      (node (ref "EPD_C7") (pin "2") (pinfunction "2_2") (pintype "passive"))
      (node (ref "J1") (pin "19") (pinfunction "19_19") (pintype "bidirectional"))
    )
    (net (code "29") (name "Net-(EPD_C8-Pad2)") (class "Default")
      (node (ref "EPD_C8") (pin "2") (pinfunction "2_2") (pintype "passive"))
      (node (ref "J1") (pin "20") (pinfunction "20_20") (pintype "bidirectional"))
    )
    (net (code "30") (name "Net-(EPD_C10-Pad2)") (class "Default")
      (node (ref "EPD_C10") (pin "2") (pinfunction "2_2") (pintype "passive"))
      (node (ref "J1") (pin "22") (pinfunction "22_22") (pintype "bidirectional"))
    )
    (net (code "31") (name "Net-(EPD_C12-Pad2)") (class "Default")
      (node (ref "EPD_C12") (pin "2") (pinfunction "2_2") (pintype "passive"))
      (node (ref "J1") (pin "24") (pinfunction "24_24") (pintype "bidirectional"))
    )
    (net (code "32") (name "Net-(IC1-CT)") (class "Default")
      (node (ref "C_DELAY") (pin "1") (pinfunction "1_1") (pintype "passive"))
      (node (ref "IC1") (pin "5") (pinfunction "CT_5") (pintype "bidirectional"))
    )
    (net (code "33") (name "Net-(J2-PadA5)") (class "Default")
      (node (ref "J2") (pin "A5") (pinfunction "A5_A5") (pintype "bidirectional"))
      (node (ref "R2-USB1") (pin "2") (pinfunction "2_2") (pintype "passive"))
    )
    (net (code "34") (name "Net-(J2-PadB5)") (class "Default")
      (node (ref "J2") (pin "B5") (pinfunction "B5_B5") (pintype "bidirectional"))
      (node (ref "R2-USB") (pin "1") (pinfunction "1_1") (pintype "passive"))
    )
    (net (code "35") (name "Net-(MCP73831-PROG)") (class "Default")
      (node (ref "MCP73831") (pin "5") (pinfunction "PROG_5") (pintype "input"))
      (node (ref "R2_BAT") (pin "2") (pinfunction "2_2") (pintype "passive"))
    )
    (net (code "36") (name "Net-(MCP73831-STAT)") (class "Default")
      (node (ref "MCP73831") (pin "1") (pinfunction "STAT_1") (pintype "output"))
      (node (ref "R1_BAT") (pin "2") (pinfunction "2_2") (pintype "passive"))
    )
    (net (code "37") (name "PREVGH") (class "Default")
      (node (ref "D5") (pin "1") (pinfunction "K_1") (pintype "bidirectional"))
      (node (ref "EPD_C9") (pin "2") (pinfunction "2_2") (pintype "passive"))
      (node (ref "J1") (pin "21") (pinfunction "21_21") (pintype "bidirectional"))
    )
    (net (code "38") (name "PREVGL") (class "Default")
      (node (ref "D4") (pin "2") (pinfunction "A_2") (pintype "bidirectional"))
      (node (ref "EPD_C11") (pin "2") (pinfunction "2_2") (pintype "passive"))
      (node (ref "J1") (pin "23") (pinfunction "23_23") (pintype "bidirectional"))
    )
    (net (code "39") (name "RESE") (class "Default")
      (node (ref "J1") (pin "3") (pinfunction "3_3") (pintype "bidirectional"))
      (node (ref "Q3") (pin "2") (pinfunction "S_2") (pintype "bidirectional"))
      (node (ref "R3") (pin "2") (pinfunction "2_2") (pintype "passive"))
    )
    (net (code "40") (name "RESE'") (class "Default")
      (node (ref "R2") (pin "2") (pinfunction "2_2") (pintype "passive"))
      (node (ref "R3") (pin "1") (pinfunction "1_1") (pintype "passive"))
      (node (ref "SJ1") (pin "2") (pinfunction "2_2") (pintype "passive"))
    )
    (net (code "41") (name "RESET") (class "Default")
      (node (ref "C5") (pin "1") (pinfunction "1_1") (pintype "passive"))
      (node (ref "IC1") (pin "1") (pinfunction "VOUT_1") (pintype "bidirectional"))
      (node (ref "RESET_BUTTON") (pin "3") (pinfunction "3_3") (pintype "passive"))
      (node (ref "RESET_BUTTON") (pin "4") (pinfunction "4_4") (pintype "passive"))
      (node (ref "R_RESET") (pin "1") (pinfunction "1_1") (pintype "passive"))
      (node (ref "U2") (pin "3") (pinfunction "EN_3") (pintype "input"))
    )
    (net (code "42") (name "RTC_RST") (class "Default")
      (node (ref "U2") (pin "16") (pinfunction "IO18_16") (pintype "bidirectional"))
      (node (ref "U3") (pin "4") (pinfunction "~{RST}_4") (pintype "input"))
    )
    (net (code "43") (name "RX") (class "Default")
      (node (ref "TP2") (pin "TP") (pinfunction "TP_TP") (pintype "input"))
      (node (ref "U2") (pin "24") (pinfunction "RXD0/GPIO17_24") (pintype "bidirectional"))
    )
    (net (code "44") (name "SCK") (class "Default")
      (node (ref "D10") (pin "1") (pinfunction "1_1") (pintype "passive"))
      (node (ref "J1") (pin "13") (pinfunction "13_13") (pintype "bidirectional"))
      (node (ref "J4") (pin "P5") (pinfunction "CLK_P5") (pintype "bidirectional"))
      (node (ref "R6") (pin "1") (pinfunction "1_1") (pintype "passive"))
      (node (ref "TP8") (pin "TP") (pinfunction "TP_TP") (pintype "input"))
      (node (ref "U1") (pin "6") (pinfunction "CLK_6") (pintype "input"))
      (node (ref "U2") (pin "6") (pinfunction "IO6_6") (pintype "bidirectional"))
    )
    (net (code "45") (name "SCL") (class "Default")
      (node (ref "J3") (pin "4") (pinfunction "4_4") (pintype "passive"))
      (node (ref "R2_PINH") (pin "1") (pinfunction "1_1") (pintype "passive"))
      (node (ref "SENSOR2") (pin "4") (pinfunction "SCK_4") (pintype "input"))
      (node (ref "U2") (pin "20") (pinfunction "IO22_20") (pintype "bidirectional"))
      (node (ref "U3") (pin "16") (pinfunction "SCL_16") (pintype "input"))
      (node (ref "U4") (pin "7") (pinfunction "SCL_7") (pintype "input"))
    )
    (net (code "46") (name "SDA") (class "Default")
      (node (ref "J3") (pin "3") (pinfunction "3_3") (pintype "passive"))
      (node (ref "R1_PINH") (pin "1") (pinfunction "1_1") (pintype "passive"))
      (node (ref "SENSOR2") (pin "3") (pinfunction "SDI_3") (pintype "bidirectional"))
      (node (ref "U2") (pin "19") (pinfunction "IO21_19") (pintype "bidirectional"))
      (node (ref "U3") (pin "15") (pinfunction "SDA_15") (pintype "bidirectional"))
      (node (ref "U4") (pin "8") (pinfunction "SDA_8") (pintype "bidirectional"))
    )
    (net (code "47") (name "SRC") (class "Default")
      (node (ref "C4") (pin "2") (pinfunction "2_2") (pintype "passive"))
      (node (ref "D5") (pin "2") (pinfunction "A_2") (pintype "bidirectional"))
      (node (ref "L1") (pin "1") (pinfunction "1_1") (pintype "passive"))
      (node (ref "Q3") (pin "3") (pinfunction "D_3") (pintype "bidirectional"))
    )
    (net (code "48") (name "SS_SD") (class "Default")
      (node (ref "D8") (pin "1") (pinfunction "1_1") (pintype "passive"))
      (node (ref "J4") (pin "P2") (pinfunction "CD/DAT3_P2") (pintype "bidirectional"))
      (node (ref "R10") (pin "1") (pinfunction "1_1") (pintype "passive"))
      (node (ref "U2") (pin "4") (pinfunction "IO4_4") (pintype "bidirectional"))
    )
    (net (code "49") (name "TX") (class "Default")
      (node (ref "TP1") (pin "TP") (pinfunction "TP_TP") (pintype "input"))
      (node (ref "U2") (pin "25") (pinfunction "TXD0/GPIO16_25") (pintype "bidirectional"))
    )
    (net (code "50") (name "USB_D+") (class "Default")
      (node (ref "D1") (pin "1") (pinfunction "I/O1_1_1") (pintype "bidirectional"))
      (node (ref "U2") (pin "14") (pinfunction "IO13_14") (pintype "bidirectional"))
    )
    (net (code "51") (name "USB_D-") (class "Default")
      (node (ref "D1") (pin "3") (pinfunction "I/O2_1_3") (pintype "bidirectional"))
      (node (ref "U2") (pin "13") (pinfunction "IO12_13") (pintype "bidirectional"))
    )
    (net (code "52") (name "VBAT") (class "Default")
      (node (ref "C2_BAT") (pin "1") (pinfunction "1_1") (pintype "passive"))
      (node (ref "MCP73831") (pin "3") (pinfunction "VBAT_3") (pintype "power_in"))
      (node (ref "Q1") (pin "3") (pinfunction "D_3") (pintype "bidirectional"))
      (node (ref "TP3") (pin "TP") (pinfunction "TP_TP") (pintype "input"))
      (node (ref "U4") (pin "2") (pinfunction "CELL_2") (pintype "power_in"))
      (node (ref "U4") (pin "3") (pinfunction "VDD_3") (pintype "power_in"))
    )
    (net (code "53") (name "VBUS") (class "Default")
      (node (ref "C1_BAT") (pin "1") (pinfunction "1_1") (pintype "passive"))
      (node (ref "C4_USB") (pin "1") (pinfunction "1_1") (pintype "passive"))
      (node (ref "C5_USB") (pin "1") (pinfunction "1_1") (pintype "passive"))
      (node (ref "CHG_LED") (pin "A") (pinfunction "A_A") (pintype "passive"))
      (node (ref "D1") (pin "5") (pinfunction "VBUS_5") (pintype "bidirectional"))
      (node (ref "D2") (pin "2") (pinfunction "ANODE_2") (pintype "bidirectional"))
      (node (ref "MCP73831") (pin "4") (pinfunction "VIN_4") (pintype "power_in"))
      (node (ref "PFMF.050.1") (pin "2") (pinfunction "2_2") (pintype "passive"))
      (node (ref "Q1") (pin "1") (pinfunction "G_1") (pintype "bidirectional"))
      (node (ref "R1_PWRUSB") (pin "2") (pinfunction "2_2") (pintype "passive"))
      (node (ref "TP14") (pin "TP") (pinfunction "TP_TP") (pintype "input"))
    )
    (net (code "54") (name "VRTC") (class "Default")
      (node (ref "C10_SUPERCAP") (pin "2") (pinfunction "2_2") (pintype "passive"))
      (node (ref "C8") (pin "1") (pinfunction "1_1") (pintype "passive"))
      (node (ref "R_CAPACITOR") (pin "1") (pinfunction "1_1") (pintype "passive"))
      (node (ref "U3") (pin "14") (pinfunction "VBAT_14") (pintype "power_in"))
    )
    (net (code "55") (name "VUSB") (class "Default")
      (node (ref "J2") (pin "A4") (pinfunction "A4_A4") (pintype "bidirectional"))
      (node (ref "J2") (pin "A9") (pinfunction "A9_A9") (pintype "bidirectional"))
      (node (ref "J2") (pin "B4") (pinfunction "B4_B4") (pintype "bidirectional"))
      (node (ref "J2") (pin "B9") (pinfunction "B9_B9") (pintype "bidirectional"))
      (node (ref "PFMF.050.1") (pin "1") (pinfunction "1_1") (pintype "passive"))
    )
    (net (code "56") (name "unconnected-(IC1-NC-Pad4)") (class "Default")
      (node (ref "IC1") (pin "4") (pinfunction "NC_4") (pintype "no_connect"))
    )
    (net (code "57") (name "unconnected-(IC4-NC-Pad4)") (class "Default")
      (node (ref "IC4") (pin "4") (pinfunction "NC_4") (pintype "no_connect"))
    )
    (net (code "58") (name "unconnected-(J1-Pad1)") (class "Default")
      (node (ref "J1") (pin "1") (pinfunction "1_1") (pintype "bidirectional"))
    )
    (net (code "59") (name "unconnected-(J1-Pad6)") (class "Default")
      (node (ref "J1") (pin "6") (pinfunction "6_6") (pintype "bidirectional"))
    )
    (net (code "60") (name "unconnected-(J1-Pad7)") (class "Default")
      (node (ref "J1") (pin "7") (pinfunction "7_7") (pintype "bidirectional"))
    )
    (net (code "61") (name "unconnected-(J2-PadA8)") (class "Default")
      (node (ref "J2") (pin "A8") (pinfunction "A8_A8") (pintype "bidirectional"))
    )
    (net (code "62") (name "unconnected-(J2-PadB8)") (class "Default")
      (node (ref "J2") (pin "B8") (pinfunction "B8_B8") (pintype "bidirectional"))
    )
    (net (code "63") (name "unconnected-(J4-DAT1-PadP8)") (class "Default")
      (node (ref "J4") (pin "P8") (pinfunction "DAT1_P8") (pintype "bidirectional"))
    )
    (net (code "64") (name "unconnected-(J4-DAT2-PadP1)") (class "Default")
      (node (ref "J4") (pin "P1") (pinfunction "DAT2_P1") (pintype "bidirectional"))
    )
    (net (code "65") (name "unconnected-(J4-DETECTION_1-PadS1)") (class "Default")
      (node (ref "J4") (pin "S1") (pinfunction "DETECTION_1_S1") (pintype "bidirectional"))
    )
    (net (code "66") (name "unconnected-(J4-DETECTION_2-PadS2)") (class "Default")
      (node (ref "J4") (pin "S2") (pinfunction "DETECTION_2_S2") (pintype "bidirectional"))
    )
    (net (code "67") (name "unconnected-(U2-NC-Pad22)") (class "Default")
      (node (ref "U2") (pin "22") (pinfunction "NC_22") (pintype "no_connect"))
    )
    (net (code "68") (name "unconnected-(U4-~{ALERT}-Pad5)") (class "Default")
      (node (ref "U4") (pin "5") (pinfunction "~{ALERT}_5") (pintype "output"))
    )
  )
)
